# TRI_STATE_BUFFER.net
KiCad netlist of a schematic drawn in EAGLE
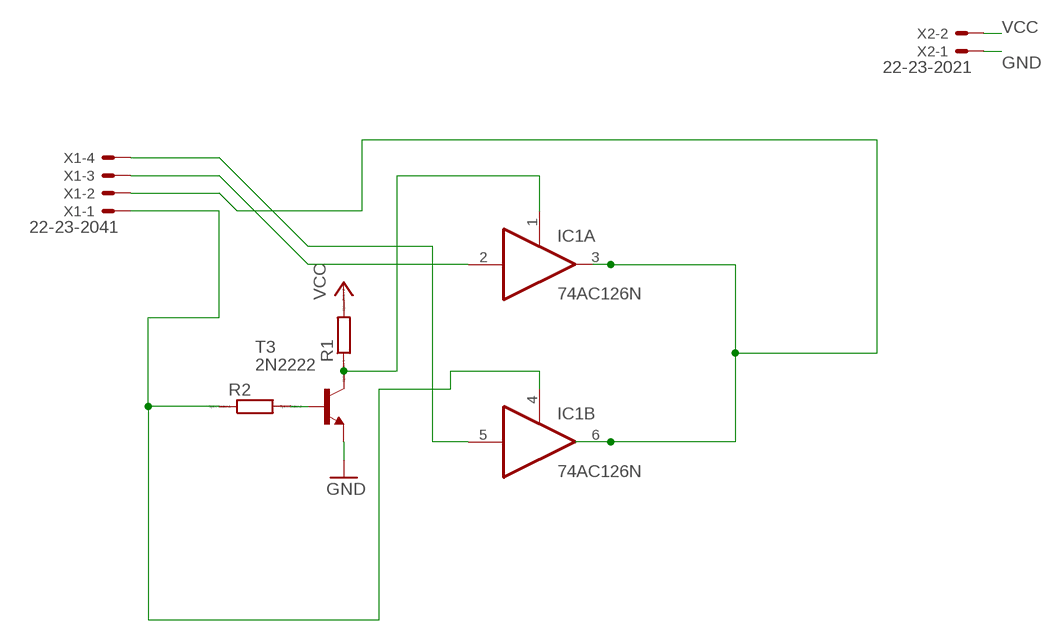
[diagram p0: schematic, sheet 1]

(export (version "E")
  (design (tool "Eeschema 10.0.6"))
  (components
    (comp (ref "IC1")
      (value "74AC126N")
      (footprint "eagle-import:DIL14")
      (libsource (lib "eagle-import") (part "74126NAC"))
    )
    (comp (ref "R1")
      (value "R0204/7")
      (footprint "eagle-import:0204_7")
      (libsource (lib "eagle-import") (part "R0204/7"))
    )
    (comp (ref "R2")
      (value "R0204/7")
      (footprint "eagle-import:0204_7")
      (libsource (lib "eagle-import") (part "R0204/7"))
    )
    (comp (ref "T3")
      (value "2N2222")
      (footprint "eagle-import:TO92-EBC-OVAL")
      (libsource (lib "eagle-import") (part "2N2222"))
    )
    (comp (ref "X1")
      (value "22-23-2041")
      (footprint "eagle-import:22-23-2041")
      (fields (field (name "MF") "MOLEX"))
      (libsource (lib "eagle-import") (part "22-23-2041"))
    )
    (comp (ref "X2")
      (value "22-23-2021")
      (footprint "eagle-import:22-23-2021")
      (fields (field (name "MF") "MOLEX"))
      (libsource (lib "eagle-import") (part "22-23-2021"))
    )
  )
  (nets
    (net (code "1") (name "GND") (class "Default")
      (node (ref "T3") (pin "E") (pinfunction "E_E") (pintype "passive"))
      (node (ref "X2") (pin "1") (pinfunction "S_1") (pintype "passive"))
    )
    (net (code "2") (name "Net-(IC1A-I)") (class "Default")
      (node (ref "IC1") (pin "2") (pinfunction "I_2") (pintype "input"))
      (node (ref "X1") (pin "3") (pinfunction "S_3") (pintype "passive"))
    )
    (net (code "3") (name "Net-(IC1A-O)") (class "Default")
      (node (ref "IC1") (pin "3") (pinfunction "O_3") (pintype "output"))
      (node (ref "IC1") (pin "6") (pinfunction "O_6") (pintype "output"))
      (node (ref "X1") (pin "2") (pinfunction "S_2") (pintype "passive"))
    )
    (net (code "4") (name "Net-(IC1A-OE)") (class "Default")
      (node (ref "IC1") (pin "1") (pinfunction "OE_1") (pintype "input"))
      (node (ref "R1") (pin "1") (pinfunction "1_1") (pintype "passive"))
      (node (ref "T3") (pin "C") (pinfunction "C_C") (pintype "passive"))
    )
    (net (code "5") (name "Net-(IC1B-I)") (class "Default")
      (node (ref "IC1") (pin "5") (pinfunction "I_5") (pintype "input"))
      (node (ref "X1") (pin "4") (pinfunction "S_4") (pintype "passive"))
    )
    (net (code "6") (name "Net-(IC1B-OE)") (class "Default")
      (node (ref "IC1") (pin "4") (pinfunction "OE_4") (pintype "input"))
      (node (ref "R2") (pin "1") (pinfunction "1_1") (pintype "passive"))
      (node (ref "X1") (pin "1") (pinfunction "S_1") (pintype "passive"))
    )
    (net (code "7") (name "Net-(R2-Pad2)") (class "Default")
      (node (ref "R2") (pin "2") (pinfunction "2_2") (pintype "passive"))
      (node (ref "T3") (pin "B") (pinfunction "B_B") (pintype "passive"))
    )
    (net (code "8") (name "VCC") (class "Default")
      (node (ref "R1") (pin "2") (pinfunction "2_2") (pintype "passive"))
      (node (ref "X2") (pin "2") (pinfunction "S_2") (pintype "passive"))
    )
  )
)
